# brick_i2c_mpu9250.net
KiCad netlist of a schematic drawn in EAGLE
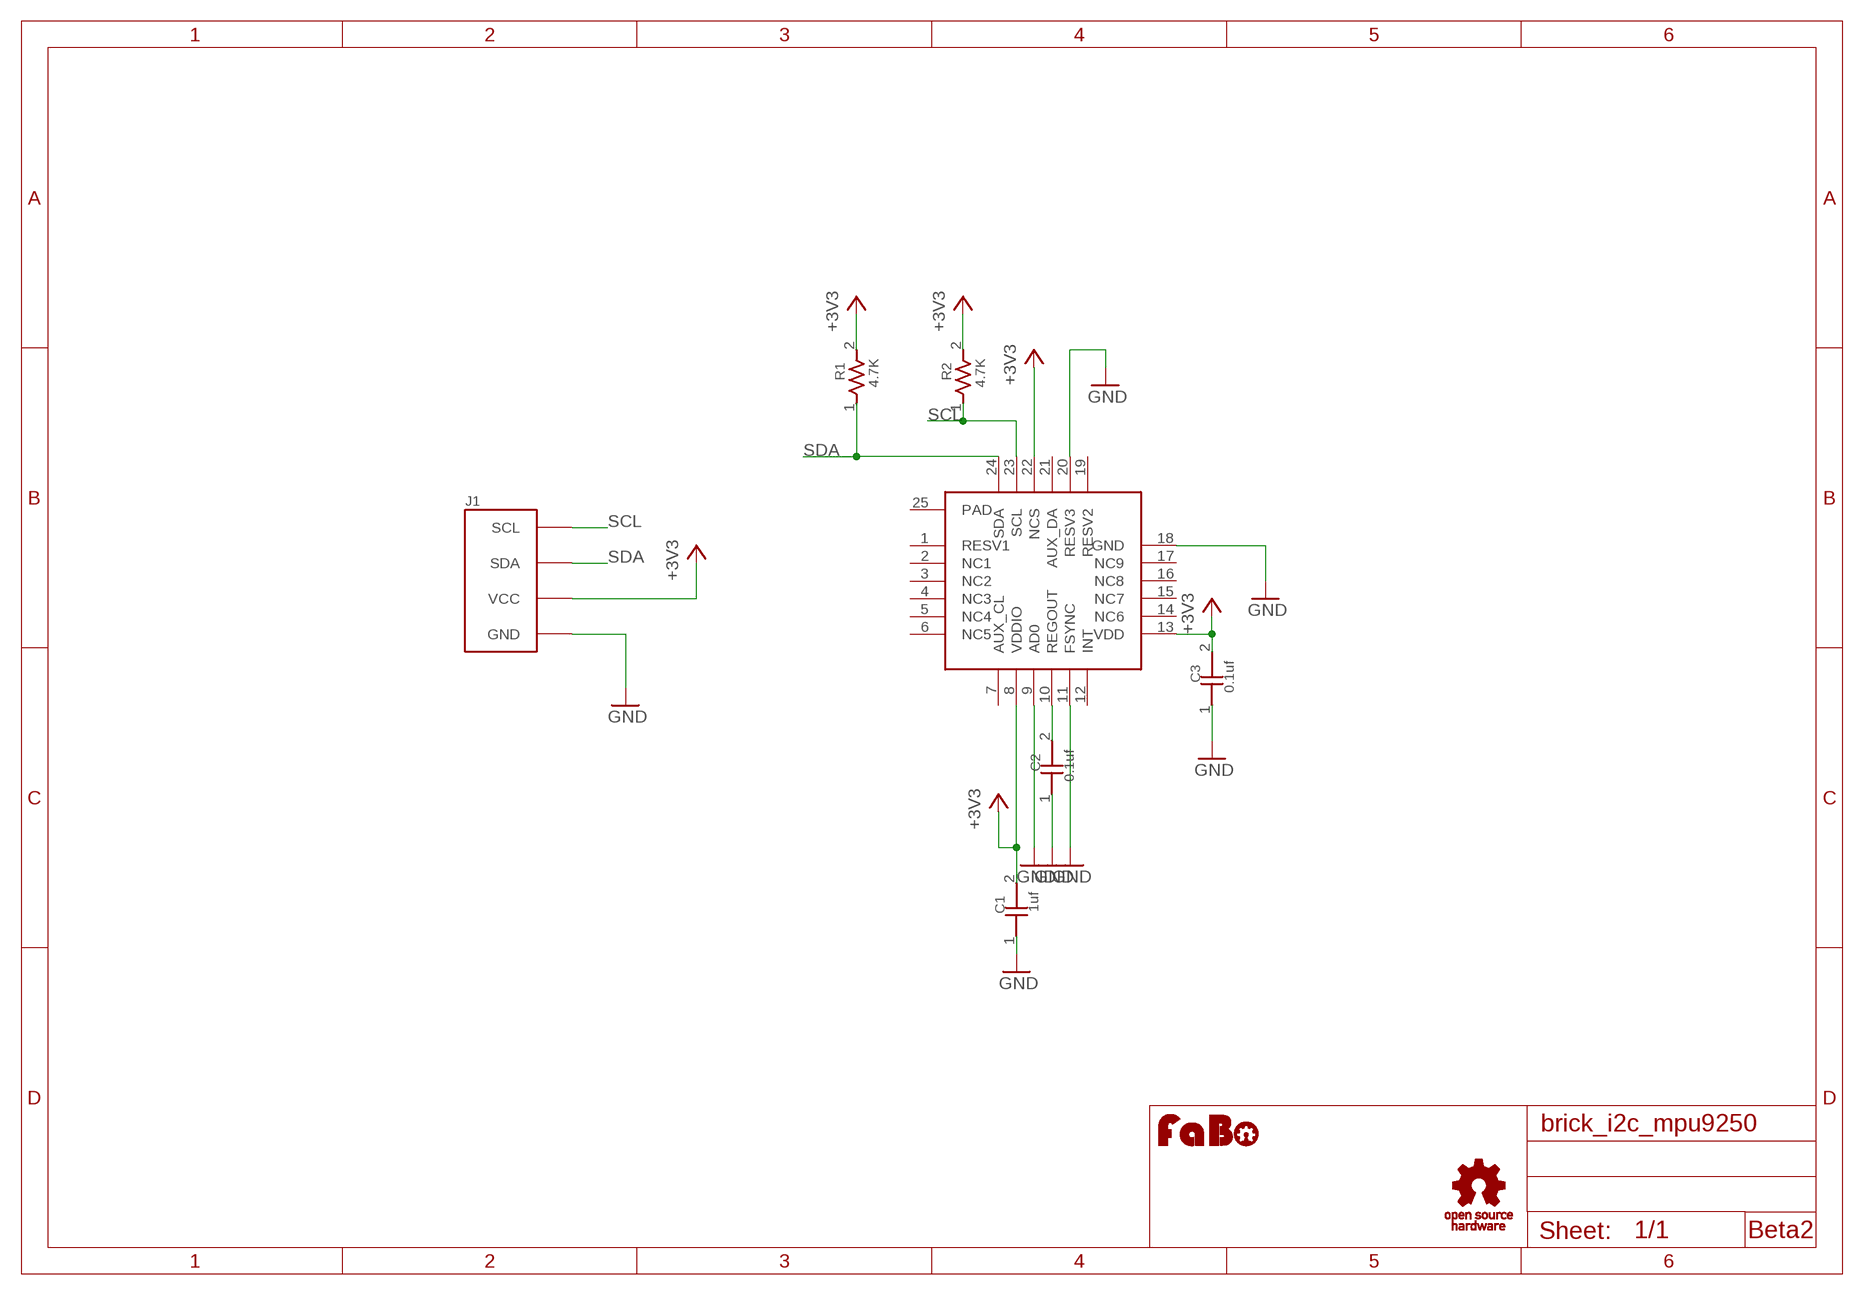
[diagram p0: schematic, sheet 1]

(export (version "E")
  (design (tool "Eeschema 10.0.6"))
  (components
    (comp (ref "C1")
      (value "1uf")
      (footprint "eagle-import:0603")
      (libsource (lib "eagle-import") (part "CAPACITOR0603"))
    )
    (comp (ref "C2")
      (value "0.1uf")
      (footprint "eagle-import:0603")
      (libsource (lib "eagle-import") (part "CAPACITOR0603"))
    )
    (comp (ref "C3")
      (value "0.1uf")
      (footprint "eagle-import:0603")
      (libsource (lib "eagle-import") (part "CAPACITOR0603"))
    )
    (comp (ref "J1")
      (value "BRICK_I2C")
      (footprint "eagle-import:BRICK_I2C")
      (libsource (lib "eagle-import") (part "BRICK_I2C"))
    )
    (comp (ref "R1")
      (value "4.7K")
      (footprint "eagle-import:0603")
      (libsource (lib "eagle-import") (part "RESISTOR0603"))
    )
    (comp (ref "R2")
      (value "4.7K")
      (footprint "eagle-import:0603")
      (libsource (lib "eagle-import") (part "RESISTOR0603"))
    )
    (comp (ref "U$1")
      (value "INVENSENSE-MPU9250")
      (footprint "eagle-import:LGA-24")
      (libsource (lib "eagle-import") (part "INVENSENSE-MPU9250"))
    )
    (comp (ref "U$3")
      (value "LOGO_FABO-M")
      (footprint "eagle-import:LOGO_FABO_M")
      (libsource (lib "eagle-import") (part "LOGO_FABO-M"))
    )
    (comp (ref "U$5")
      (value "LOGO_OSHW_T-M")
      (footprint "eagle-import:LOGO_OSHW_T_M")
      (libsource (lib "eagle-import") (part "LOGO_OSHW_T-M"))
    )
  )
  (nets
    (net (code "1") (name "+3V3") (class "Default")
      (node (ref "C1") (pin "2") (pinfunction "2_2") (pintype "passive"))
      (node (ref "C3") (pin "2") (pinfunction "2_2") (pintype "passive"))
      (node (ref "J1") (pin "VCC") (pinfunction "VCC_VCC") (pintype "bidirectional"))
      (node (ref "R1") (pin "2") (pinfunction "2_2") (pintype "passive"))
      (node (ref "R2") (pin "2") (pinfunction "2_2") (pintype "passive"))
      (node (ref "U$1") (pin "13") (pinfunction "VDD_13") (pintype "bidirectional"))
      (node (ref "U$1") (pin "22") (pinfunction "NCS_22") (pintype "bidirectional"))
      (node (ref "U$1") (pin "8") (pinfunction "VDDIO_8") (pintype "bidirectional"))
    )
    (net (code "2") (name "/SCL") (class "Default")
      (node (ref "J1") (pin "SCL") (pinfunction "SCL_SCL") (pintype "bidirectional"))
      (node (ref "R2") (pin "1") (pinfunction "1_1") (pintype "passive"))
      (node (ref "U$1") (pin "23") (pinfunction "SCL_23") (pintype "bidirectional"))
    )
    (net (code "3") (name "/SDA") (class "Default")
      (node (ref "J1") (pin "SDA") (pinfunction "SDA_SDA") (pintype "bidirectional"))
      (node (ref "R1") (pin "1") (pinfunction "1_1") (pintype "passive"))
      (node (ref "U$1") (pin "24") (pinfunction "SDA_24") (pintype "bidirectional"))
    )
    (net (code "4") (name "GND") (class "Default")
      (node (ref "C1") (pin "1") (pinfunction "1_1") (pintype "passive"))
      (node (ref "C2") (pin "1") (pinfunction "1_1") (pintype "passive"))
      (node (ref "C3") (pin "1") (pinfunction "1_1") (pintype "passive"))
      (node (ref "J1") (pin "GND") (pinfunction "GND_GND") (pintype "bidirectional"))
      (node (ref "U$1") (pin "11") (pinfunction "FSYNC_11") (pintype "bidirectional"))
      (node (ref "U$1") (pin "18") (pinfunction "GND_18") (pintype "bidirectional"))
      (node (ref "U$1") (pin "20") (pinfunction "RESV3_20") (pintype "bidirectional"))
      (node (ref "U$1") (pin "9") (pinfunction "AD0_9") (pintype "bidirectional"))
    )
    (net (code "5") (name "Net-(U$1-REGOUT)") (class "Default")
      (node (ref "C2") (pin "2") (pinfunction "2_2") (pintype "passive"))
      (node (ref "U$1") (pin "10") (pinfunction "REGOUT_10") (pintype "bidirectional"))
    )
    (net (code "6") (name "unconnected-(U$1-AUX_CL-Pad7)") (class "Default")
      (node (ref "U$1") (pin "7") (pinfunction "AUX_CL_7") (pintype "bidirectional"))
    )
    (net (code "7") (name "unconnected-(U$1-AUX_DA-Pad21)") (class "Default")
      (node (ref "U$1") (pin "21") (pinfunction "AUX_DA_21") (pintype "bidirectional"))
    )
    (net (code "8") (name "unconnected-(U$1-INT-Pad12)") (class "Default")
      (node (ref "U$1") (pin "12") (pinfunction "INT_12") (pintype "bidirectional"))
    )
    (net (code "9") (name "unconnected-(U$1-NC1-Pad2)") (class "Default")
      (node (ref "U$1") (pin "2") (pinfunction "NC1_2") (pintype "bidirectional"))
    )
    (net (code "10") (name "unconnected-(U$1-NC2-Pad3)") (class "Default")
      (node (ref "U$1") (pin "3") (pinfunction "NC2_3") (pintype "bidirectional"))
    )
    (net (code "11") (name "unconnected-(U$1-NC3-Pad4)") (class "Default")
      (node (ref "U$1") (pin "4") (pinfunction "NC3_4") (pintype "bidirectional"))
    )
    (net (code "12") (name "unconnected-(U$1-NC4-Pad5)") (class "Default")
      (node (ref "U$1") (pin "5") (pinfunction "NC4_5") (pintype "bidirectional"))
    )
    (net (code "13") (name "unconnected-(U$1-NC5-Pad6)") (class "Default")
      (node (ref "U$1") (pin "6") (pinfunction "NC5_6") (pintype "bidirectional"))
    )
    (net (code "14") (name "unconnected-(U$1-NC6-Pad14)") (class "Default")
      (node (ref "U$1") (pin "14") (pinfunction "NC6_14") (pintype "bidirectional"))
    )
    (net (code "15") (name "unconnected-(U$1-NC7-Pad15)") (class "Default")
      (node (ref "U$1") (pin "15") (pinfunction "NC7_15") (pintype "bidirectional"))
    )
    (net (code "16") (name "unconnected-(U$1-NC8-Pad16)") (class "Default")
      (node (ref "U$1") (pin "16") (pinfunction "NC8_16") (pintype "bidirectional"))
    )
    (net (code "17") (name "unconnected-(U$1-NC9-Pad17)") (class "Default")
      (node (ref "U$1") (pin "17") (pinfunction "NC9_17") (pintype "bidirectional"))
    )
    (net (code "18") (name "unconnected-(U$1-PAD-Pad25)") (class "Default")
      (node (ref "U$1") (pin "25") (pinfunction "PAD_25") (pintype "bidirectional"))
    )
    (net (code "19") (name "unconnected-(U$1-RESV1-Pad1)") (class "Default")
      (node (ref "U$1") (pin "1") (pinfunction "RESV1_1") (pintype "bidirectional"))
    )
    (net (code "20") (name "unconnected-(U$1-RESV2-Pad19)") (class "Default")
      (node (ref "U$1") (pin "19") (pinfunction "RESV2_19") (pintype "bidirectional"))
    )
  )
)
